# zSum_4_io_board_rev_A.net
KiCad netlist of a schematic drawn in EAGLE
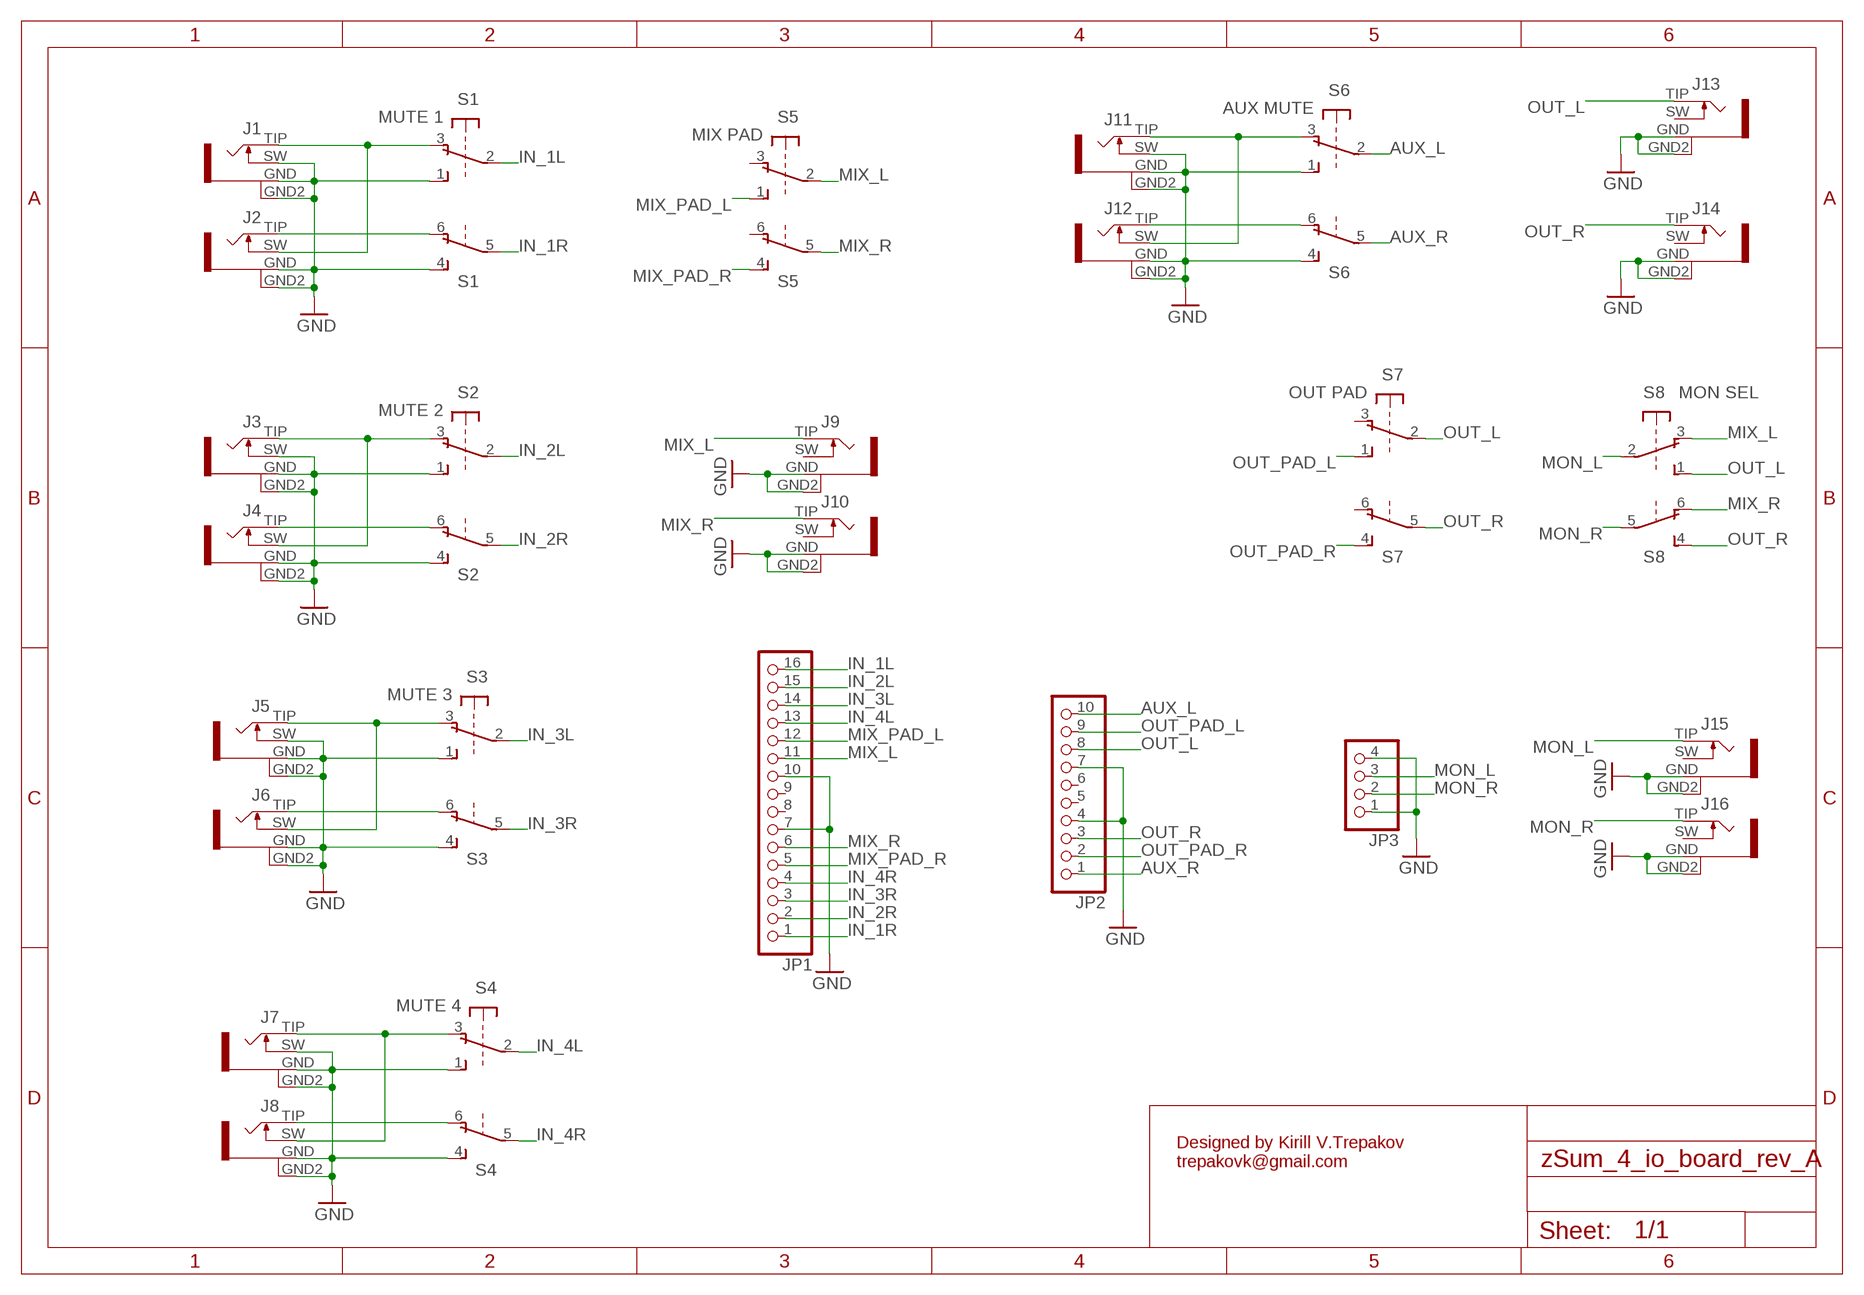
[diagram p0: schematic, sheet 1]

(export (version "E")
  (design (tool "Eeschema 10.0.6"))
  (components
    (comp (ref "J1")
      (value "PJ301WQP")
      (footprint "eagle-import:WQP_PJ_301BM")
      (libsource (lib "eagle-import") (part "PJ301WQP"))
    )
    (comp (ref "J2")
      (value "PJ301WQP")
      (footprint "eagle-import:WQP_PJ_301BM")
      (libsource (lib "eagle-import") (part "PJ301WQP"))
    )
    (comp (ref "J3")
      (value "PJ301WQP")
      (footprint "eagle-import:WQP_PJ_301BM")
      (libsource (lib "eagle-import") (part "PJ301WQP"))
    )
    (comp (ref "J4")
      (value "PJ301WQP")
      (footprint "eagle-import:WQP_PJ_301BM")
      (libsource (lib "eagle-import") (part "PJ301WQP"))
    )
    (comp (ref "J5")
      (value "PJ301WQP")
      (footprint "eagle-import:WQP_PJ_301BM")
      (libsource (lib "eagle-import") (part "PJ301WQP"))
    )
    (comp (ref "J6")
      (value "PJ301WQP")
      (footprint "eagle-import:WQP_PJ_301BM")
      (libsource (lib "eagle-import") (part "PJ301WQP"))
    )
    (comp (ref "J7")
      (value "PJ301WQP")
      (footprint "eagle-import:WQP_PJ_301BM")
      (libsource (lib "eagle-import") (part "PJ301WQP"))
    )
    (comp (ref "J8")
      (value "PJ301WQP")
      (footprint "eagle-import:WQP_PJ_301BM")
      (libsource (lib "eagle-import") (part "PJ301WQP"))
    )
    (comp (ref "J9")
      (value "PJ301WQP")
      (footprint "eagle-import:WQP_PJ_301BM")
      (libsource (lib "eagle-import") (part "PJ301WQP"))
    )
    (comp (ref "J10")
      (value "PJ301WQP")
      (footprint "eagle-import:WQP_PJ_301BM")
      (libsource (lib "eagle-import") (part "PJ301WQP"))
    )
    (comp (ref "J11")
      (value "PJ301WQP")
      (footprint "eagle-import:WQP_PJ_301BM")
      (libsource (lib "eagle-import") (part "PJ301WQP"))
    )
    (comp (ref "J12")
      (value "PJ301WQP")
      (footprint "eagle-import:WQP_PJ_301BM")
      (libsource (lib "eagle-import") (part "PJ301WQP"))
    )
    (comp (ref "J13")
      (value "PJ301WQP")
      (footprint "eagle-import:WQP_PJ_301BM")
      (libsource (lib "eagle-import") (part "PJ301WQP"))
    )
    (comp (ref "J14")
      (value "PJ301WQP")
      (footprint "eagle-import:WQP_PJ_301BM")
      (libsource (lib "eagle-import") (part "PJ301WQP"))
    )
    (comp (ref "J15")
      (value "PJ301WQP")
      (footprint "eagle-import:WQP_PJ_301BM")
      (libsource (lib "eagle-import") (part "PJ301WQP"))
    )
    (comp (ref "J16")
      (value "PJ301WQP")
      (footprint "eagle-import:WQP_PJ_301BM")
      (libsource (lib "eagle-import") (part "PJ301WQP"))
    )
    (comp (ref "JP1")
      (value "PINHD-1X16")
      (footprint "eagle-import:1X16_")
      (libsource (lib "eagle-import") (part "PINHD-1X16"))
    )
    (comp (ref "JP2")
      (value "PINHD-1X10")
      (footprint "eagle-import:1X10_")
      (libsource (lib "eagle-import") (part "PINHD-1X10"))
    )
    (comp (ref "JP3")
      (value "PINHD-1X4")
      (footprint "eagle-import:1X04")
      (libsource (lib "eagle-import") (part "PINHD-1X4"))
    )
    (comp (ref "S1")
      (value "MUTE 1")
      (footprint "eagle-import:9077-2")
      (libsource (lib "eagle-import") (part "9077-2"))
    )
    (comp (ref "S2")
      (value "MUTE 2")
      (footprint "eagle-import:9077-2")
      (libsource (lib "eagle-import") (part "9077-2"))
    )
    (comp (ref "S3")
      (value "MUTE 3")
      (footprint "eagle-import:9077-2")
      (libsource (lib "eagle-import") (part "9077-2"))
    )
    (comp (ref "S4")
      (value "MUTE 4")
      (footprint "eagle-import:9077-2")
      (libsource (lib "eagle-import") (part "9077-2"))
    )
    (comp (ref "S5")
      (value "MIX PAD")
      (footprint "eagle-import:9077-2")
      (libsource (lib "eagle-import") (part "9077-2"))
    )
    (comp (ref "S6")
      (value "AUX MUTE")
      (footprint "eagle-import:9077-2")
      (libsource (lib "eagle-import") (part "9077-2"))
    )
    (comp (ref "S7")
      (value "OUT PAD")
      (footprint "eagle-import:9077-2")
      (libsource (lib "eagle-import") (part "9077-2"))
    )
    (comp (ref "S8")
      (value "MON SEL")
      (footprint "eagle-import:9077-2")
      (libsource (lib "eagle-import") (part "9077-2"))
    )
  )
  (nets
    (net (code "1") (name "/AUX_L") (class "Default")
      (node (ref "JP2") (pin "10") (pinfunction "10_10") (pintype "passive"))
      (node (ref "S6") (pin "2") (pinfunction "P_2") (pintype "passive"))
    )
    (net (code "2") (name "/AUX_R") (class "Default")
      (node (ref "JP2") (pin "1") (pinfunction "1_1") (pintype "passive"))
      (node (ref "S6") (pin "5") (pinfunction "P_5") (pintype "passive"))
    )
    (net (code "3") (name "/IN_1L") (class "Default")
      (node (ref "JP1") (pin "16") (pinfunction "16_16") (pintype "passive"))
      (node (ref "S1") (pin "2") (pinfunction "P_2") (pintype "passive"))
    )
    (net (code "4") (name "/IN_1R") (class "Default")
      (node (ref "JP1") (pin "1") (pinfunction "1_1") (pintype "passive"))
      (node (ref "S1") (pin "5") (pinfunction "P_5") (pintype "passive"))
    )
    (net (code "5") (name "/IN_2L") (class "Default")
      (node (ref "JP1") (pin "15") (pinfunction "15_15") (pintype "passive"))
      (node (ref "S2") (pin "2") (pinfunction "P_2") (pintype "passive"))
    )
    (net (code "6") (name "/IN_2R") (class "Default")
      (node (ref "JP1") (pin "2") (pinfunction "2_2") (pintype "passive"))
      (node (ref "S2") (pin "5") (pinfunction "P_5") (pintype "passive"))
    )
    (net (code "7") (name "/IN_3L") (class "Default")
      (node (ref "JP1") (pin "14") (pinfunction "14_14") (pintype "passive"))
      (node (ref "S3") (pin "2") (pinfunction "P_2") (pintype "passive"))
    )
    (net (code "8") (name "/IN_3R") (class "Default")
      (node (ref "JP1") (pin "3") (pinfunction "3_3") (pintype "passive"))
      (node (ref "S3") (pin "5") (pinfunction "P_5") (pintype "passive"))
    )
    (net (code "9") (name "/IN_4L") (class "Default")
      (node (ref "JP1") (pin "13") (pinfunction "13_13") (pintype "passive"))
      (node (ref "S4") (pin "2") (pinfunction "P_2") (pintype "passive"))
    )
    (net (code "10") (name "/IN_4R") (class "Default")
      (node (ref "JP1") (pin "4") (pinfunction "4_4") (pintype "passive"))
      (node (ref "S4") (pin "5") (pinfunction "P_5") (pintype "passive"))
    )
    (net (code "11") (name "/MIX_L") (class "Default")
      (node (ref "J9") (pin "TIP") (pinfunction "2_TIP") (pintype "passive"))
      (node (ref "JP1") (pin "11") (pinfunction "11_11") (pintype "passive"))
      (node (ref "S5") (pin "2") (pinfunction "P_2") (pintype "passive"))
      (node (ref "S8") (pin "3") (pinfunction "O_3") (pintype "passive"))
    )
    (net (code "12") (name "/MIX_PAD_L") (class "Default")
      (node (ref "JP1") (pin "12") (pinfunction "12_12") (pintype "passive"))
      (node (ref "S5") (pin "1") (pinfunction "S_1") (pintype "passive"))
    )
    (net (code "13") (name "/MIX_PAD_R") (class "Default")
      (node (ref "JP1") (pin "5") (pinfunction "5_5") (pintype "passive"))
      (node (ref "S5") (pin "4") (pinfunction "S_4") (pintype "passive"))
    )
    (net (code "14") (name "/MIX_R") (class "Default")
      (node (ref "J10") (pin "TIP") (pinfunction "2_TIP") (pintype "passive"))
      (node (ref "JP1") (pin "6") (pinfunction "6_6") (pintype "passive"))
      (node (ref "S5") (pin "5") (pinfunction "P_5") (pintype "passive"))
      (node (ref "S8") (pin "6") (pinfunction "O_6") (pintype "passive"))
    )
    (net (code "15") (name "/MON_L") (class "Default")
      (node (ref "J15") (pin "TIP") (pinfunction "2_TIP") (pintype "passive"))
      (node (ref "JP3") (pin "3") (pinfunction "3_3") (pintype "passive"))
      (node (ref "S8") (pin "2") (pinfunction "P_2") (pintype "passive"))
    )
    (net (code "16") (name "/MON_R") (class "Default")
      (node (ref "J16") (pin "TIP") (pinfunction "2_TIP") (pintype "passive"))
      (node (ref "JP3") (pin "2") (pinfunction "2_2") (pintype "passive"))
      (node (ref "S8") (pin "5") (pinfunction "P_5") (pintype "passive"))
    )
    (net (code "17") (name "/OUT_L") (class "Default")
      (node (ref "J13") (pin "TIP") (pinfunction "2_TIP") (pintype "passive"))
      (node (ref "JP2") (pin "8") (pinfunction "8_8") (pintype "passive"))
      (node (ref "S7") (pin "2") (pinfunction "P_2") (pintype "passive"))
      (node (ref "S8") (pin "1") (pinfunction "S_1") (pintype "passive"))
    )
    (net (code "18") (name "/OUT_PAD_L") (class "Default")
      (node (ref "JP2") (pin "9") (pinfunction "9_9") (pintype "passive"))
      (node (ref "S7") (pin "1") (pinfunction "S_1") (pintype "passive"))
    )
    (net (code "19") (name "/OUT_PAD_R") (class "Default")
      (node (ref "JP2") (pin "2") (pinfunction "2_2") (pintype "passive"))
      (node (ref "S7") (pin "4") (pinfunction "S_4") (pintype "passive"))
    )
    (net (code "20") (name "/OUT_R") (class "Default")
      (node (ref "J14") (pin "TIP") (pinfunction "2_TIP") (pintype "passive"))
      (node (ref "JP2") (pin "3") (pinfunction "3_3") (pintype "passive"))
      (node (ref "S7") (pin "5") (pinfunction "P_5") (pintype "passive"))
      (node (ref "S8") (pin "4") (pinfunction "S_4") (pintype "passive"))
    )
    (net (code "21") (name "GND") (class "Default")
      (node (ref "J1") (pin "GND") (pinfunction "1_GND") (pintype "passive"))
      (node (ref "J1") (pin "GND2") (pinfunction "4_GND2") (pintype "passive"))
      (node (ref "J1") (pin "SW") (pinfunction "3_SW") (pintype "passive"))
      (node (ref "J10") (pin "GND") (pinfunction "1_GND") (pintype "passive"))
      (node (ref "J10") (pin "GND2") (pinfunction "4_GND2") (pintype "passive"))
      (node (ref "J11") (pin "GND") (pinfunction "1_GND") (pintype "passive"))
      (node (ref "J11") (pin "GND2") (pinfunction "4_GND2") (pintype "passive"))
      (node (ref "J11") (pin "SW") (pinfunction "3_SW") (pintype "passive"))
      (node (ref "J12") (pin "GND") (pinfunction "1_GND") (pintype "passive"))
      (node (ref "J12") (pin "GND2") (pinfunction "4_GND2") (pintype "passive"))
      (node (ref "J13") (pin "GND") (pinfunction "1_GND") (pintype "passive"))
      (node (ref "J13") (pin "GND2") (pinfunction "4_GND2") (pintype "passive"))
      (node (ref "J14") (pin "GND") (pinfunction "1_GND") (pintype "passive"))
      (node (ref "J14") (pin "GND2") (pinfunction "4_GND2") (pintype "passive"))
      (node (ref "J15") (pin "GND") (pinfunction "1_GND") (pintype "passive"))
      (node (ref "J15") (pin "GND2") (pinfunction "4_GND2") (pintype "passive"))
      (node (ref "J16") (pin "GND") (pinfunction "1_GND") (pintype "passive"))
      (node (ref "J16") (pin "GND2") (pinfunction "4_GND2") (pintype "passive"))
      (node (ref "J2") (pin "GND") (pinfunction "1_GND") (pintype "passive"))
      (node (ref "J2") (pin "GND2") (pinfunction "4_GND2") (pintype "passive"))
      (node (ref "J3") (pin "GND") (pinfunction "1_GND") (pintype "passive"))
      (node (ref "J3") (pin "GND2") (pinfunction "4_GND2") (pintype "passive"))
      (node (ref "J3") (pin "SW") (pinfunction "3_SW") (pintype "passive"))
      (node (ref "J4") (pin "GND") (pinfunction "1_GND") (pintype "passive"))
      (node (ref "J4") (pin "GND2") (pinfunction "4_GND2") (pintype "passive"))
      (node (ref "J5") (pin "GND") (pinfunction "1_GND") (pintype "passive"))
      (node (ref "J5") (pin "GND2") (pinfunction "4_GND2") (pintype "passive"))
      (node (ref "J5") (pin "SW") (pinfunction "3_SW") (pintype "passive"))
      (node (ref "J6") (pin "GND") (pinfunction "1_GND") (pintype "passive"))
      (node (ref "J6") (pin "GND2") (pinfunction "4_GND2") (pintype "passive"))
      (node (ref "J7") (pin "GND") (pinfunction "1_GND") (pintype "passive"))
      (node (ref "J7") (pin "GND2") (pinfunction "4_GND2") (pintype "passive"))
      (node (ref "J7") (pin "SW") (pinfunction "3_SW") (pintype "passive"))
      (node (ref "J8") (pin "GND") (pinfunction "1_GND") (pintype "passive"))
      (node (ref "J8") (pin "GND2") (pinfunction "4_GND2") (pintype "passive"))
      (node (ref "J9") (pin "GND") (pinfunction "1_GND") (pintype "passive"))
      (node (ref "J9") (pin "GND2") (pinfunction "4_GND2") (pintype "passive"))
      (node (ref "JP1") (pin "10") (pinfunction "10_10") (pintype "passive"))
      (node (ref "JP1") (pin "7") (pinfunction "7_7") (pintype "passive"))
      (node (ref "JP2") (pin "4") (pinfunction "4_4") (pintype "passive"))
      (node (ref "JP2") (pin "7") (pinfunction "7_7") (pintype "passive"))
      (node (ref "JP3") (pin "1") (pinfunction "1_1") (pintype "passive"))
      (node (ref "JP3") (pin "4") (pinfunction "4_4") (pintype "passive"))
      (node (ref "S1") (pin "1") (pinfunction "S_1") (pintype "passive"))
      (node (ref "S1") (pin "4") (pinfunction "S_4") (pintype "passive"))
      (node (ref "S2") (pin "1") (pinfunction "S_1") (pintype "passive"))
      (node (ref "S2") (pin "4") (pinfunction "S_4") (pintype "passive"))
      (node (ref "S3") (pin "1") (pinfunction "S_1") (pintype "passive"))
      (node (ref "S3") (pin "4") (pinfunction "S_4") (pintype "passive"))
      (node (ref "S4") (pin "1") (pinfunction "S_1") (pintype "passive"))
      (node (ref "S4") (pin "4") (pinfunction "S_4") (pintype "passive"))
      (node (ref "S6") (pin "1") (pinfunction "S_1") (pintype "passive"))
      (node (ref "S6") (pin "4") (pinfunction "S_4") (pintype "passive"))
    )
    (net (code "22") (name "Net-(J1-2)") (class "Default")
      (node (ref "J1") (pin "TIP") (pinfunction "2_TIP") (pintype "passive"))
      (node (ref "J2") (pin "SW") (pinfunction "3_SW") (pintype "passive"))
      (node (ref "S1") (pin "3") (pinfunction "O_3") (pintype "passive"))
    )
    (net (code "23") (name "Net-(J2-2)") (class "Default")
      (node (ref "J2") (pin "TIP") (pinfunction "2_TIP") (pintype "passive"))
      (node (ref "S1") (pin "6") (pinfunction "O_6") (pintype "passive"))
    )
    (net (code "24") (name "Net-(J3-2)") (class "Default")
      (node (ref "J3") (pin "TIP") (pinfunction "2_TIP") (pintype "passive"))
      (node (ref "J4") (pin "SW") (pinfunction "3_SW") (pintype "passive"))
      (node (ref "S2") (pin "3") (pinfunction "O_3") (pintype "passive"))
    )
    (net (code "25") (name "Net-(J4-2)") (class "Default")
      (node (ref "J4") (pin "TIP") (pinfunction "2_TIP") (pintype "passive"))
      (node (ref "S2") (pin "6") (pinfunction "O_6") (pintype "passive"))
    )
    (net (code "26") (name "Net-(J5-2)") (class "Default")
      (node (ref "J5") (pin "TIP") (pinfunction "2_TIP") (pintype "passive"))
      (node (ref "J6") (pin "SW") (pinfunction "3_SW") (pintype "passive"))
      (node (ref "S3") (pin "3") (pinfunction "O_3") (pintype "passive"))
    )
    (net (code "27") (name "Net-(J6-2)") (class "Default")
      (node (ref "J6") (pin "TIP") (pinfunction "2_TIP") (pintype "passive"))
      (node (ref "S3") (pin "6") (pinfunction "O_6") (pintype "passive"))
    )
    (net (code "28") (name "Net-(J7-2)") (class "Default")
      (node (ref "J7") (pin "TIP") (pinfunction "2_TIP") (pintype "passive"))
      (node (ref "J8") (pin "SW") (pinfunction "3_SW") (pintype "passive"))
      (node (ref "S4") (pin "3") (pinfunction "O_3") (pintype "passive"))
    )
    (net (code "29") (name "Net-(J8-2)") (class "Default")
      (node (ref "J8") (pin "TIP") (pinfunction "2_TIP") (pintype "passive"))
      (node (ref "S4") (pin "6") (pinfunction "O_6") (pintype "passive"))
    )
    (net (code "30") (name "Net-(J11-2)") (class "Default")
      (node (ref "J11") (pin "TIP") (pinfunction "2_TIP") (pintype "passive"))
      (node (ref "J12") (pin "SW") (pinfunction "3_SW") (pintype "passive"))
      (node (ref "S6") (pin "3") (pinfunction "O_3") (pintype "passive"))
    )
    (net (code "31") (name "Net-(J12-2)") (class "Default")
      (node (ref "J12") (pin "TIP") (pinfunction "2_TIP") (pintype "passive"))
      (node (ref "S6") (pin "6") (pinfunction "O_6") (pintype "passive"))
    )
    (net (code "32") (name "unconnected-(J9-3-PadSW)") (class "Default")
      (node (ref "J9") (pin "SW") (pinfunction "3_SW") (pintype "passive"))
    )
    (net (code "33") (name "unconnected-(J10-3-PadSW)") (class "Default")
      (node (ref "J10") (pin "SW") (pinfunction "3_SW") (pintype "passive"))
    )
    (net (code "34") (name "unconnected-(J13-3-PadSW)") (class "Default")
      (node (ref "J13") (pin "SW") (pinfunction "3_SW") (pintype "passive"))
    )
    (net (code "35") (name "unconnected-(J14-3-PadSW)") (class "Default")
      (node (ref "J14") (pin "SW") (pinfunction "3_SW") (pintype "passive"))
    )
    (net (code "36") (name "unconnected-(J15-3-PadSW)") (class "Default")
      (node (ref "J15") (pin "SW") (pinfunction "3_SW") (pintype "passive"))
    )
    (net (code "37") (name "unconnected-(J16-3-PadSW)") (class "Default")
      (node (ref "J16") (pin "SW") (pinfunction "3_SW") (pintype "passive"))
    )
    (net (code "38") (name "unconnected-(JP1-Pad8)") (class "Default")
      (node (ref "JP1") (pin "8") (pinfunction "8_8") (pintype "passive"))
    )
    (net (code "39") (name "unconnected-(JP1-Pad9)") (class "Default")
      (node (ref "JP1") (pin "9") (pinfunction "9_9") (pintype "passive"))
    )
    (net (code "40") (name "unconnected-(JP2-Pad5)") (class "Default")
      (node (ref "JP2") (pin "5") (pinfunction "5_5") (pintype "passive"))
    )
    (net (code "41") (name "unconnected-(JP2-Pad6)") (class "Default")
      (node (ref "JP2") (pin "6") (pinfunction "6_6") (pintype "passive"))
    )
    (net (code "42") (name "unconnected-(S5A-O-Pad3)") (class "Default")
      (node (ref "S5") (pin "3") (pinfunction "O_3") (pintype "passive"))
    )
    (net (code "43") (name "unconnected-(S5B-O-Pad6)") (class "Default")
      (node (ref "S5") (pin "6") (pinfunction "O_6") (pintype "passive"))
    )
    (net (code "44") (name "unconnected-(S7A-O-Pad3)") (class "Default")
      (node (ref "S7") (pin "3") (pinfunction "O_3") (pintype "passive"))
    )
    (net (code "45") (name "unconnected-(S7B-O-Pad6)") (class "Default")
      (node (ref "S7") (pin "6") (pinfunction "O_6") (pintype "passive"))
    )
  )
)
